# PeltierControl.net
KiCad netlist of a schematic drawn in Altium Designer
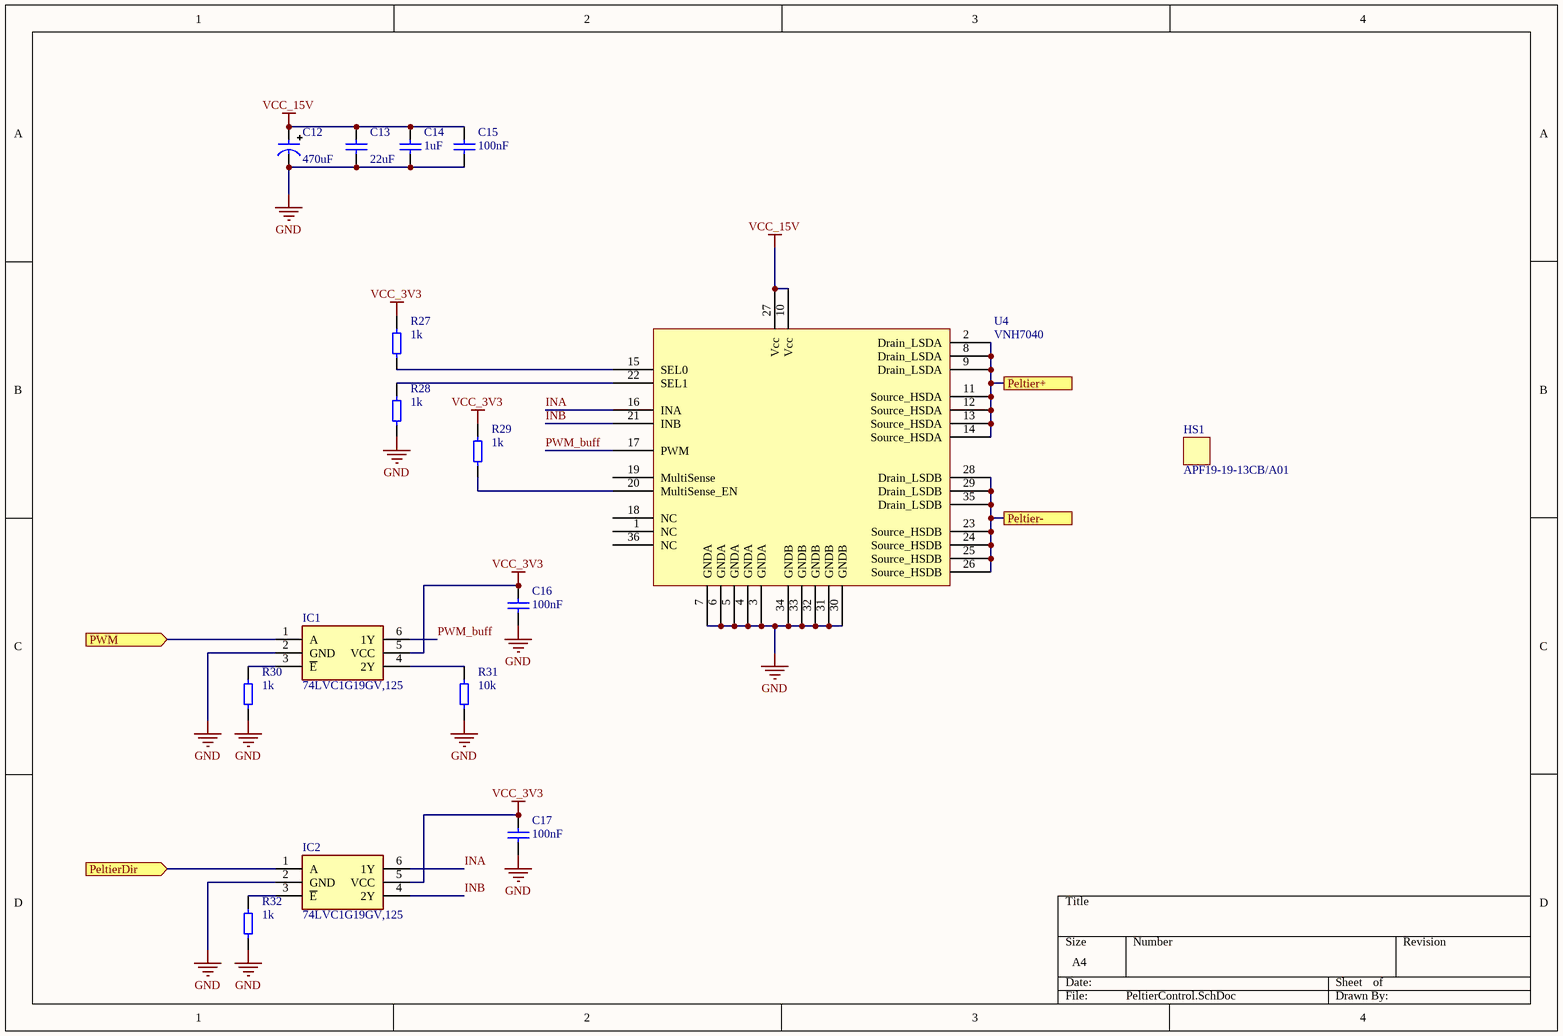
[diagram p0: PeltierControl.SchDoc]

(export (version "E")
  (design (tool "Eeschema 10.0.6"))
  (components
    (comp (ref "C12")
      (value "470uF")
      (footprint "EEV-FK1H471M")
      (description "Aluminum Electrolytic Capacitors")
      (fields (field (name "MANUFACTURER") "Panasonic") (field (name "TOLERANCE") "20%"))
      (libsource (lib "ZUIAM_LIB") (part "Panasonic_FK_PCR_6.3_Capacitor"))
    )
    (comp (ref "C13")
      (value "22uF")
      (footprint "0805-Capacitor")
      (description "Capacitor")
      (fields (field (name "PART NUMBER") "C0805"))
      (libsource (lib "ZUIAM_LIB") (part "Capacitor"))
    )
    (comp (ref "C14")
      (value "1uF")
      (footprint "0603-Capacitor")
      (description "Capacitor")
      (fields (field (name "PART NUMBER") "C0603"))
      (libsource (lib "ZUIAM_LIB") (part "Capacitor"))
    )
    (comp (ref "C15")
      (value "100nF")
      (footprint "0603-Capacitor")
      (description "Capacitor")
      (fields (field (name "PART NUMBER") "C0603"))
      (libsource (lib "ZUIAM_LIB") (part "Capacitor"))
    )
    (comp (ref "C16")
      (value "100nF")
      (footprint "0603-Capacitor")
      (description "Capacitor")
      (fields (field (name "PART NUMBER") "C0603"))
      (libsource (lib "ZUIAM_LIB") (part "Capacitor"))
    )
    (comp (ref "C17")
      (value "100nF")
      (footprint "0603-Capacitor")
      (description "Capacitor")
      (fields (field (name "PART NUMBER") "C0603"))
      (libsource (lib "ZUIAM_LIB") (part "Capacitor"))
    )
    (comp (ref "HS1")
      (value "APF19-19-13CB/A01")
      (footprint "APF19-19-13CB/A01")
      (fields (field (name "MANUFACTURER") "CTS Electronic Components"))
      (libsource (lib "mechanicalComponents") (part "heatsink"))
    )
    (comp (ref "IC1")
      (value "74LVC1G19GV,125")
      (footprint "MouserDropbox:SOT95P275X110-6N")
      (description "Integrated Circuit")
      (libsource (lib "*") (part "74LVC1G19GV,125"))
    )
    (comp (ref "IC2")
      (value "74LVC1G19GV,125")
      (footprint "MouserDropbox:SOT95P275X110-6N")
      (description "Integrated Circuit")
      (libsource (lib "*") (part "74LVC1G19GV,125"))
    )
    (comp (ref "R27")
      (value "1k")
      (footprint "0603-Resistor")
      (description "Resistor")
      (fields (field (name "PART NUMBER") "R0603"))
      (libsource (lib "ZUIAM_LIB") (part "Resistor"))
    )
    (comp (ref "R28")
      (value "1k")
      (footprint "0603-Resistor")
      (description "Resistor")
      (fields (field (name "PART NUMBER") "R0603"))
      (libsource (lib "ZUIAM_LIB") (part "Resistor"))
    )
    (comp (ref "R29")
      (value "1k")
      (footprint "0603-Resistor")
      (description "Resistor")
      (fields (field (name "PART NUMBER") "R0603"))
      (libsource (lib "ZUIAM_LIB") (part "Resistor"))
    )
    (comp (ref "R30")
      (value "1k")
      (footprint "0603-Resistor")
      (description "Resistor")
      (fields (field (name "PART NUMBER") "R0603"))
      (libsource (lib "ZUIAM_LIB") (part "Resistor"))
    )
    (comp (ref "R31")
      (value "10k")
      (footprint "0603-Resistor")
      (description "Resistor")
      (fields (field (name "PART NUMBER") "R0603"))
      (libsource (lib "ZUIAM_LIB") (part "Resistor"))
    )
    (comp (ref "R32")
      (value "1k")
      (footprint "0603-Resistor")
      (description "Resistor")
      (fields (field (name "PART NUMBER") "R0603"))
      (libsource (lib "ZUIAM_LIB") (part "Resistor"))
    )
    (comp (ref "U4")
      (value "VNH7040")
      (footprint "PowerSSO-36")
      (description "Engine driver/ H bridge")
      (fields (field (name "MANUFACTURER") "STMicroelectronics"))
      (libsource (lib "IC_lib") (part "VNH7040"))
    )
  )
  (nets
    (net (code "1") (name "/INA") (class "Default")
      (node (ref "IC2") (pin "6") (pinfunction "1Y_6") (pintype "passive"))
      (node (ref "U4") (pin "16") (pinfunction "INA_16") (pintype "passive"))
    )
    (net (code "2") (name "/INB") (class "Default")
      (node (ref "IC2") (pin "4") (pinfunction "2Y_4") (pintype "passive"))
      (node (ref "U4") (pin "21") (pinfunction "INB_21") (pintype "passive"))
    )
    (net (code "3") (name "/PWM") (class "Default")
      (node (ref "IC1") (pin "1") (pinfunction "A_1") (pintype "passive"))
    )
    (net (code "4") (name "/PWM_buff") (class "Default")
      (node (ref "IC1") (pin "6") (pinfunction "1Y_6") (pintype "passive"))
      (node (ref "U4") (pin "17") (pinfunction "PWM_17") (pintype "passive"))
    )
    (net (code "5") (name "/Peltier+") (class "Default")
      (node (ref "U4") (pin "11") (pinfunction "Source_HSDA_11") (pintype "passive"))
      (node (ref "U4") (pin "12") (pinfunction "Source_HSDA_12") (pintype "passive"))
      (node (ref "U4") (pin "13") (pinfunction "Source_HSDA_13") (pintype "passive"))
      (node (ref "U4") (pin "14") (pinfunction "Source_HSDA_14") (pintype "passive"))
      (node (ref "U4") (pin "2") (pinfunction "Drain_LSDA_2") (pintype "passive"))
      (node (ref "U4") (pin "8") (pinfunction "Drain_LSDA_8") (pintype "passive"))
      (node (ref "U4") (pin "9") (pinfunction "Drain_LSDA_9") (pintype "passive"))
    )
    (net (code "6") (name "/Peltier-") (class "Default")
      (node (ref "U4") (pin "23") (pinfunction "Source_HSDB_23") (pintype "passive"))
      (node (ref "U4") (pin "24") (pinfunction "Source_HSDB_24") (pintype "passive"))
      (node (ref "U4") (pin "25") (pinfunction "Source_HSDB_25") (pintype "passive"))
      (node (ref "U4") (pin "26") (pinfunction "Source_HSDB_26") (pintype "passive"))
      (node (ref "U4") (pin "28") (pinfunction "Drain_LSDB_28") (pintype "passive"))
      (node (ref "U4") (pin "29") (pinfunction "Drain_LSDB_29") (pintype "passive"))
      (node (ref "U4") (pin "35") (pinfunction "Drain_LSDB_35") (pintype "passive"))
    )
    (net (code "7") (name "/PeltierDir") (class "Default")
      (node (ref "IC2") (pin "1") (pinfunction "A_1") (pintype "passive"))
    )
    (net (code "8") (name "GND") (class "Default")
      (node (ref "C12") (pin "2") (pinfunction "2_2") (pintype "passive"))
      (node (ref "C13") (pin "2") (pinfunction "2_2") (pintype "passive"))
      (node (ref "C14") (pin "2") (pinfunction "2_2") (pintype "passive"))
      (node (ref "C15") (pin "2") (pinfunction "2_2") (pintype "passive"))
      (node (ref "C16") (pin "2") (pinfunction "2_2") (pintype "passive"))
      (node (ref "C17") (pin "2") (pinfunction "2_2") (pintype "passive"))
      (node (ref "IC1") (pin "2") (pinfunction "GND_2") (pintype "passive"))
      (node (ref "IC2") (pin "2") (pinfunction "GND_2") (pintype "passive"))
      (node (ref "R28") (pin "1") (pinfunction "1_1") (pintype "passive"))
      (node (ref "R30") (pin "1") (pinfunction "1_1") (pintype "passive"))
      (node (ref "R31") (pin "1") (pinfunction "1_1") (pintype "passive"))
      (node (ref "R32") (pin "1") (pinfunction "1_1") (pintype "passive"))
      (node (ref "U4") (pin "3") (pinfunction "GNDA_3") (pintype "passive"))
      (node (ref "U4") (pin "30") (pinfunction "GNDB_30") (pintype "passive"))
      (node (ref "U4") (pin "31") (pinfunction "GNDB_31") (pintype "passive"))
      (node (ref "U4") (pin "32") (pinfunction "GNDB_32") (pintype "passive"))
      (node (ref "U4") (pin "33") (pinfunction "GNDB_33") (pintype "passive"))
      (node (ref "U4") (pin "34") (pinfunction "GNDB_34") (pintype "passive"))
      (node (ref "U4") (pin "4") (pinfunction "GNDA_4") (pintype "passive"))
      (node (ref "U4") (pin "5") (pinfunction "GNDA_5") (pintype "passive"))
      (node (ref "U4") (pin "6") (pinfunction "GNDA_6") (pintype "passive"))
      (node (ref "U4") (pin "7") (pinfunction "GNDA_7") (pintype "passive"))
    )
    (net (code "9") (name "Net-(IC1-2Y)") (class "Default")
      (node (ref "IC1") (pin "4") (pinfunction "2Y_4") (pintype "passive"))
      (node (ref "R31") (pin "2") (pinfunction "2_2") (pintype "passive"))
    )
    (net (code "10") (name "Net-(IC1-~{E})") (class "Default")
      (node (ref "IC1") (pin "3") (pinfunction "~{E}_3") (pintype "passive"))
      (node (ref "R30") (pin "2") (pinfunction "2_2") (pintype "passive"))
    )
    (net (code "11") (name "Net-(IC2-~{E})") (class "Default")
      (node (ref "IC2") (pin "3") (pinfunction "~{E}_3") (pintype "passive"))
      (node (ref "R32") (pin "2") (pinfunction "2_2") (pintype "passive"))
    )
    (net (code "12") (name "Net-(U4-MultiSense_EN)") (class "Default")
      (node (ref "R29") (pin "1") (pinfunction "1_1") (pintype "passive"))
      (node (ref "U4") (pin "20") (pinfunction "MultiSense_EN_20") (pintype "passive"))
    )
    (net (code "13") (name "Net-(U4-SEL0)") (class "Default")
      (node (ref "R27") (pin "1") (pinfunction "1_1") (pintype "passive"))
      (node (ref "U4") (pin "15") (pinfunction "SEL0_15") (pintype "passive"))
    )
    (net (code "14") (name "Net-(U4-SEL1)") (class "Default")
      (node (ref "R28") (pin "2") (pinfunction "2_2") (pintype "passive"))
      (node (ref "U4") (pin "22") (pinfunction "SEL1_22") (pintype "passive"))
    )
    (net (code "15") (name "VCC_3V3") (class "Default")
      (node (ref "C16") (pin "1") (pinfunction "1_1") (pintype "passive"))
      (node (ref "C17") (pin "1") (pinfunction "1_1") (pintype "passive"))
      (node (ref "IC1") (pin "5") (pinfunction "VCC_5") (pintype "passive"))
      (node (ref "IC2") (pin "5") (pinfunction "VCC_5") (pintype "passive"))
      (node (ref "R27") (pin "2") (pinfunction "2_2") (pintype "passive"))
      (node (ref "R29") (pin "2") (pinfunction "2_2") (pintype "passive"))
    )
    (net (code "16") (name "VCC_15V") (class "Default")
      (node (ref "C12") (pin "1") (pinfunction "1_1") (pintype "passive"))
      (node (ref "C13") (pin "1") (pinfunction "1_1") (pintype "passive"))
      (node (ref "C14") (pin "1") (pinfunction "1_1") (pintype "passive"))
      (node (ref "C15") (pin "1") (pinfunction "1_1") (pintype "passive"))
      (node (ref "U4") (pin "10") (pinfunction "Vcc_10") (pintype "passive"))
      (node (ref "U4") (pin "27") (pinfunction "Vcc_27") (pintype "passive"))
    )
    (net (code "17") (name "unconnected-(U4-MultiSense-Pad19)") (class "Default")
      (node (ref "U4") (pin "19") (pinfunction "MultiSense_19") (pintype "passive"))
    )
    (net (code "18") (name "unconnected-(U4-NC-Pad1)") (class "Default")
      (node (ref "U4") (pin "1") (pinfunction "NC_1") (pintype "passive"))
    )
    (net (code "19") (name "unconnected-(U4-NC-Pad18)") (class "Default")
      (node (ref "U4") (pin "18") (pinfunction "NC_18") (pintype "passive"))
    )
    (net (code "20") (name "unconnected-(U4-NC-Pad36)") (class "Default")
      (node (ref "U4") (pin "36") (pinfunction "NC_36") (pintype "passive"))
    )
  )
)
